# GP1A57.net
KiCad netlist of a schematic drawn in EAGLE
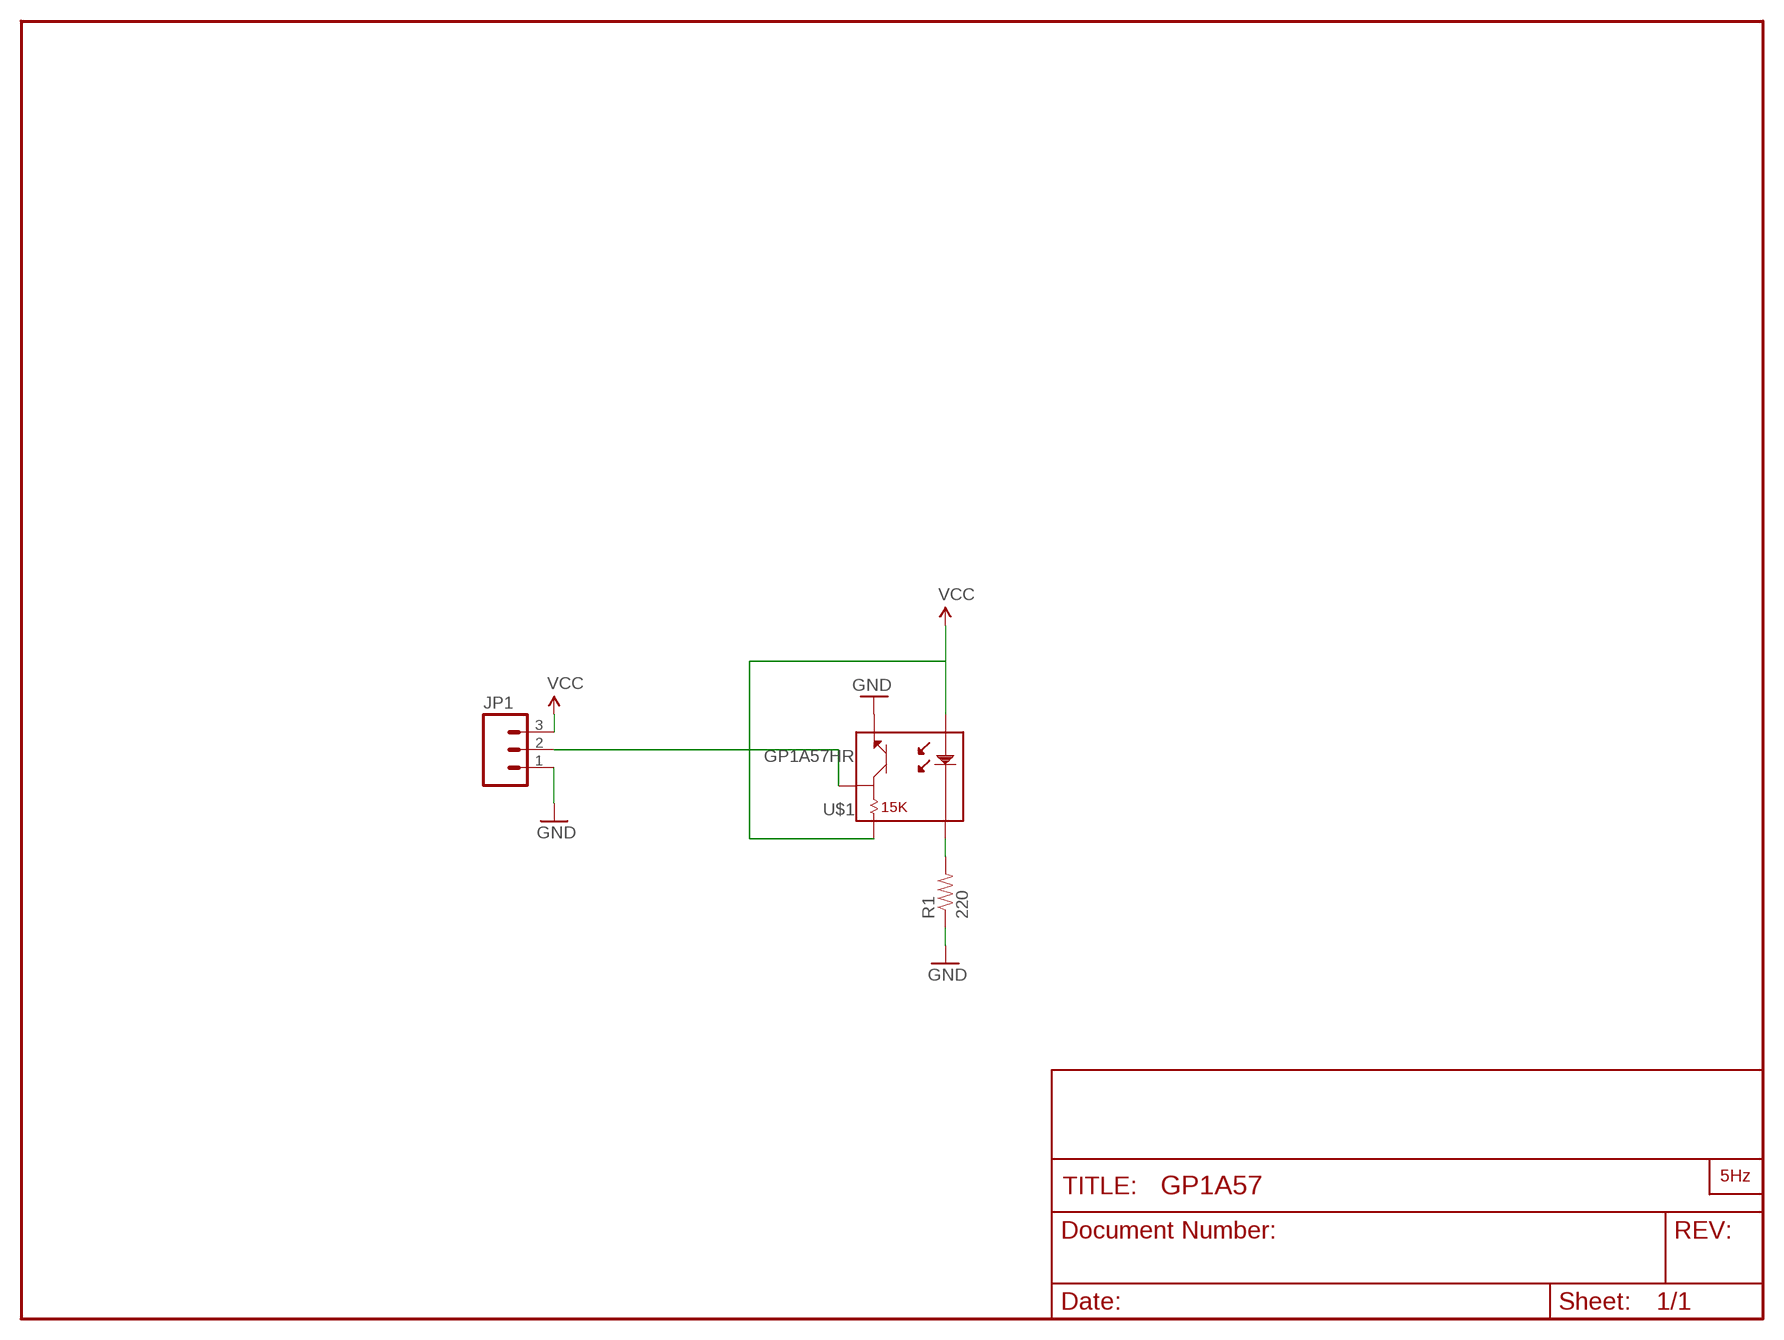
[diagram p0: schematic, sheet 1]

(export (version "E")
  (design (tool "Eeschema 10.0.6"))
  (components
    (comp (ref "JP1")
      (value "M03PTH")
      (footprint "eagle-import:1X03")
      (libsource (lib "eagle-import") (part "M03PTH"))
    )
    (comp (ref "R1")
      (value "220")
      (footprint "eagle-import:AXIAL-0.4")
      (libsource (lib "eagle-import") (part "RESISTORPTH-1/4W"))
    )
    (comp (ref "U$1")
      (value "GP1A57HR")
      (footprint "eagle-import:GP1A57HR")
      (libsource (lib "eagle-import") (part "GP1A57HR"))
    )
    (comp (ref "U$2")
      (value "LOGO2_SILKL10MM")
      (footprint "eagle-import:LARGO2_10MM")
      (libsource (lib "eagle-import") (part "LOGO2_SILKL10MM"))
    )
  )
  (nets
    (net (code "1") (name "GND") (class "Default")
      (node (ref "JP1") (pin "1") (pinfunction "1_1") (pintype "passive"))
      (node (ref "R1") (pin "P$1") (pinfunction "1_P$1") (pintype "passive"))
      (node (ref "U$1") (pin "5") (pinfunction "5_5") (pintype "bidirectional"))
    )
    (net (code "2") (name "Net-(JP1-Pad2)") (class "Default")
      (node (ref "JP1") (pin "2") (pinfunction "2_2") (pintype "passive"))
      (node (ref "U$1") (pin "4") (pinfunction "4_4") (pintype "bidirectional"))
    )
    (net (code "3") (name "Net-(R1-2)") (class "Default")
      (node (ref "R1") (pin "P$2") (pinfunction "2_P$2") (pintype "passive"))
      (node (ref "U$1") (pin "2") (pinfunction "2_2") (pintype "bidirectional"))
    )
    (net (code "4") (name "VCC") (class "Default")
      (node (ref "JP1") (pin "3") (pinfunction "3_3") (pintype "passive"))
      (node (ref "U$1") (pin "1") (pinfunction "1_1") (pintype "bidirectional"))
      (node (ref "U$1") (pin "3") (pinfunction "3_3") (pintype "bidirectional"))
    )
  )
)
